# Adafruit_Feather_M0_Basic_rev_C.net
KiCad netlist of a schematic drawn in Altium Designer
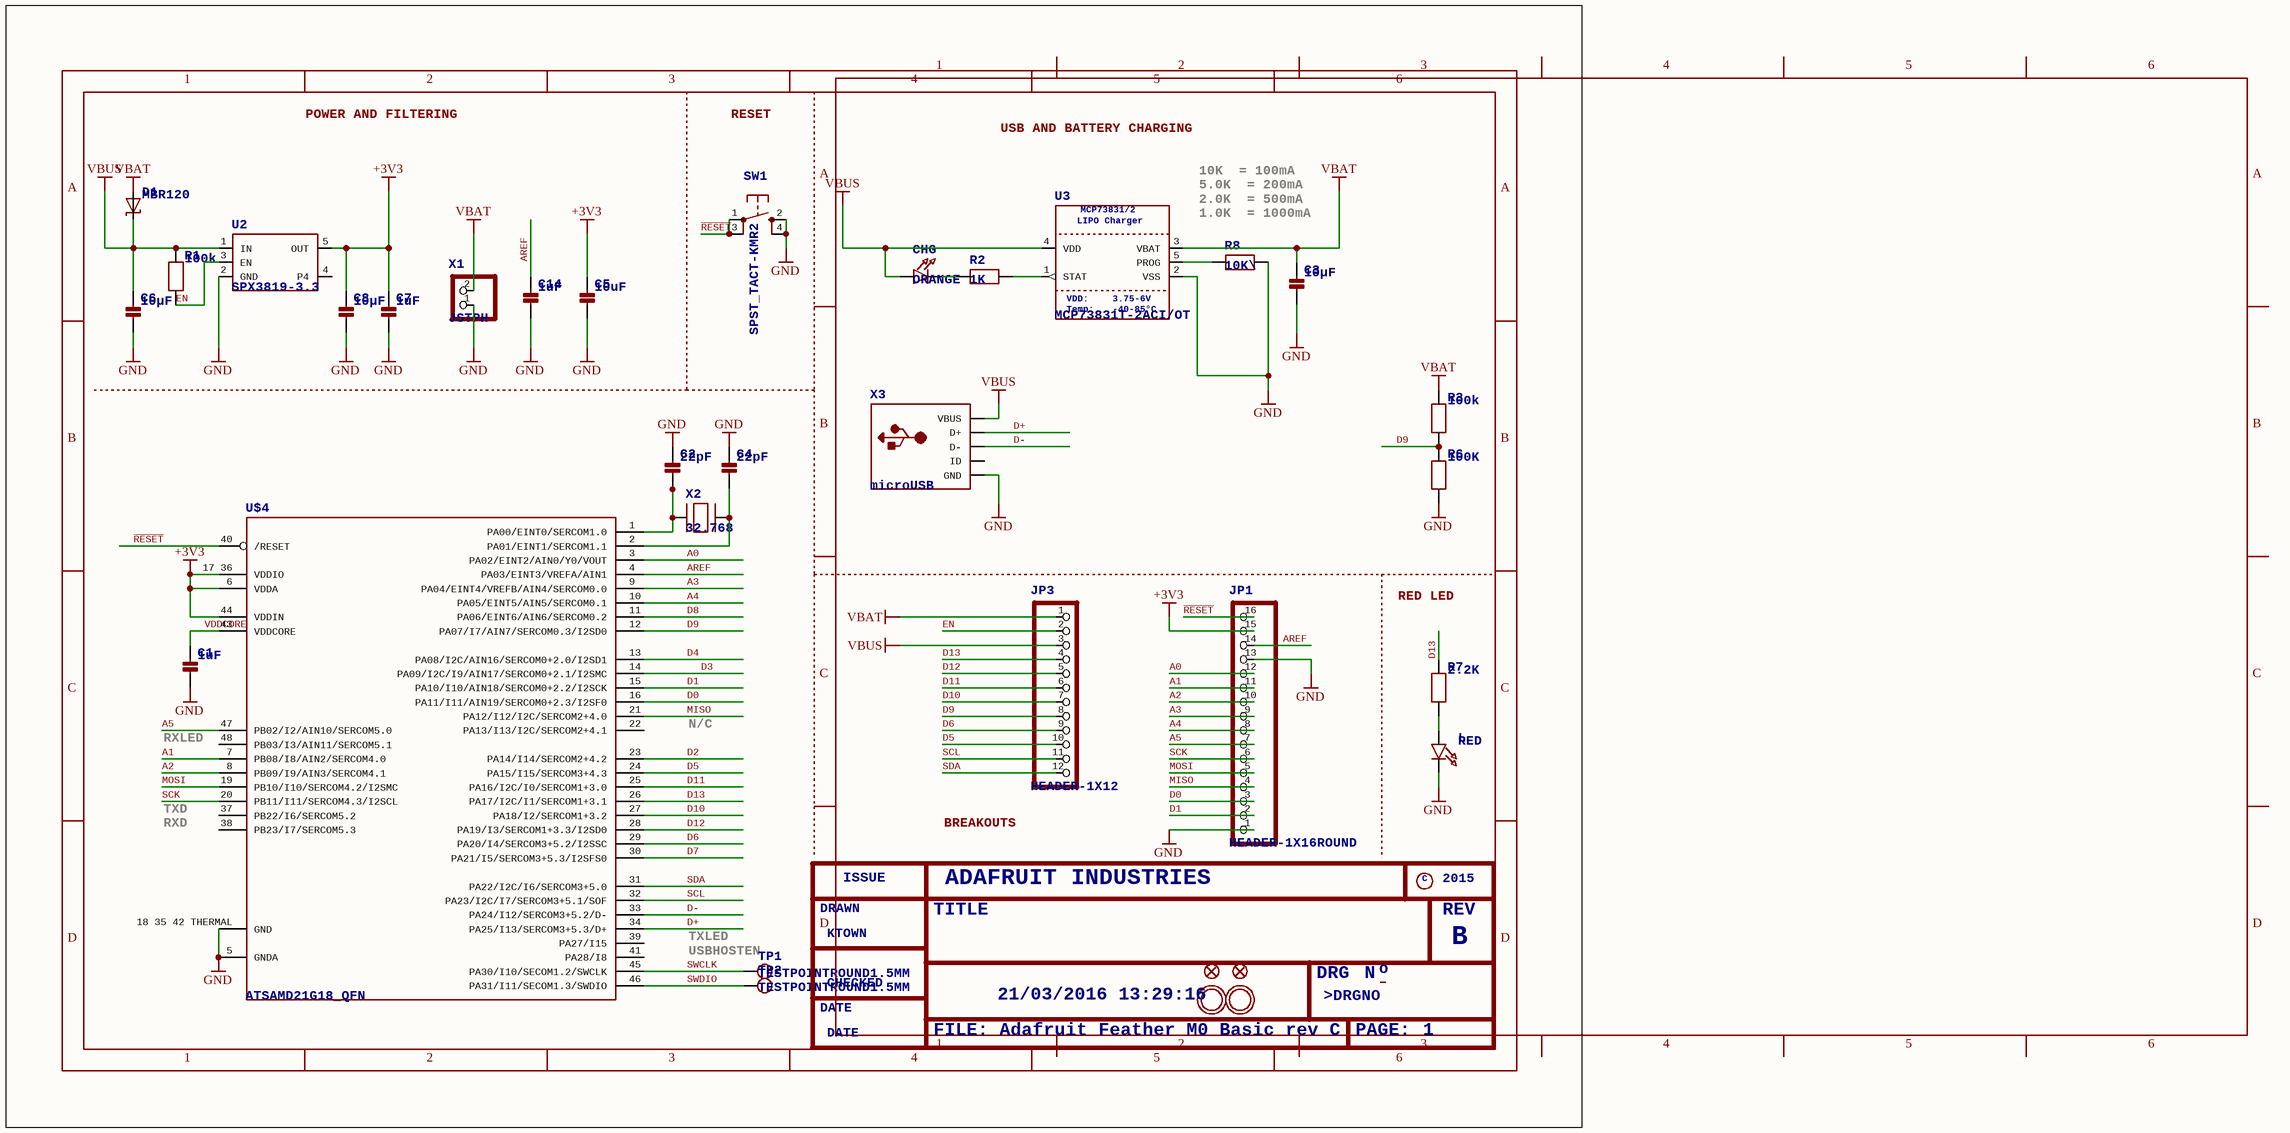
[diagram p0: Adafruit Feather M0 Basic rev C.SchDoc]

(export (version "E")
  (design (tool "Eeschema 10.0.6"))
  (components
    (comp (ref "C1")
      (value "1uF")
      (footprint "0603-NO")
      (fields (field (name "DRAWN") "KTOWN"))
      (libsource (lib "microbuilder") (part "CAP_CERAMIC0603_NO"))
    )
    (comp (ref "C2")
      (value "22pF")
      (footprint "0603-NO")
      (fields (field (name "DRAWN") "KTOWN"))
      (libsource (lib "") (part "CAP_CERAMIC0603_NO_1"))
    )
    (comp (ref "C3")
      (value "10µF")
      (footprint "0805-NO")
      (fields (field (name "DRAWN") "KTOWN"))
      (libsource (lib "microbuilder") (part "CAP_CERAMIC0805-NOOUTLINE"))
    )
    (comp (ref "C4")
      (value "22pF")
      (footprint "0603-NO")
      (fields (field (name "DRAWN") "KTOWN"))
      (libsource (lib "") (part "CAP_CERAMIC0603_NO_1"))
    )
    (comp (ref "C5")
      (value "10uF")
      (footprint "0805-NO")
      (fields (field (name "DRAWN") "KTOWN"))
      (libsource (lib "microbuilder") (part "CAP_CERAMIC0805-NOOUTLINE"))
    )
    (comp (ref "C6")
      (value "10µF")
      (footprint "0805-NO")
      (fields (field (name "DRAWN") "KTOWN"))
      (libsource (lib "microbuilder") (part "CAP_CERAMIC0805-NOOUTLINE"))
    )
    (comp (ref "C7")
      (value "1uF")
      (footprint "0603-NO")
      (fields (field (name "DRAWN") "KTOWN"))
      (libsource (lib "microbuilder") (part "CAP_CERAMIC0603_NO"))
    )
    (comp (ref "C8")
      (value "10µF")
      (footprint "0805-NO")
      (fields (field (name "DRAWN") "KTOWN"))
      (libsource (lib "microbuilder") (part "CAP_CERAMIC0805-NOOUTLINE"))
    )
    (comp (ref "C14")
      (value "1uF")
      (footprint "0603-NO")
      (fields (field (name "DRAWN") "KTOWN"))
      (libsource (lib "microbuilder") (part "CAP_CERAMIC0603_NO"))
    )
    (comp (ref "CHG")
      (value "ORANGE")
      (footprint "CHIPLED_0805_NOOUTLINE")
      (fields (field (name "DRAWN") "KTOWN"))
      (libsource (lib "") (part "LED0805_NOOUTLINE_1"))
    )
    (comp (ref "D1")
      (value "MBR120")
      (footprint "SOD-123")
      (fields (field (name "DRAWN") "KTOWN"))
      (libsource (lib "microbuilder") (part "DIODE-SCHOTTKYSOD-123"))
    )
    (comp (ref "FRAME1")
      (value "FRAME_A4")
      (description "FRAME   DIN A4, landscape with location and doc. field")
      (fields
        (field (name "SHEET") "1")
        (field (name "REV") "REV")
        (field (name "TITLE") "TITLE")
        (field (name "DRG") "DRG")
        (field (name "O") "o")
        (field (name "DRAWING_NAME") "Adafruit Feather M0 Basic rev C")
        (field (name "N") "N")
        (field (name "LAST_DATE_TIME") "21/03/2016 13:29:16")
        (field (name "2015") "2015")
        (field (name "C") "C")
        (field (name "ISSUE") "ISSUE")
        (field (name "DRAWN") "DRAWN")
        (field (name "DATE") "DATE")
        (field (name "COMPANY") "ADAFRUIT INDUSTRIES")
        (field (name "FILE") "FILE:")
        (field (name "PAGE") "PAGE:")
        (field (name "DRAWN_1") "KTOWN")
        (field (name "CHECKED") "CHECKED")
        (field (name "DATE_1") "DATE")
        (field (name "DRGNO") ">DRGNO")
        (field (name "REV_1") "B")
      )
      (libsource (lib "microbuilder") (part "FRAME_A4"))
    )
    (comp (ref "JP1")
      (value "HEADER-1X16ROUND")
      (footprint "1X16_ROUND")
      (description "PIN HEADER")
      (fields (field (name "DRAWN") "KTOWN"))
      (libsource (lib "microbuilder") (part "HEADER-1X16ROUND"))
    )
    (comp (ref "JP3")
      (value "HEADER-1X12")
      (footprint "1X12_ROUND")
      (fields (field (name "DRAWN") "KTOWN"))
      (libsource (lib "microbuilder") (part "HEADER-1X12"))
    )
    (comp (ref "L")
      (value "RED")
      (footprint "CHIPLED_0805_NOOUTLINE")
      (fields (field (name "DRAWN") "KTOWN"))
      (libsource (lib "microbuilder") (part "LED0805_NOOUTLINE"))
    )
    (comp (ref "R1")
      (value "100k")
      (footprint "0603-NO")
      (fields (field (name "DRAWN") "KTOWN"))
      (libsource (lib "microbuilder") (part "RESISTOR_0603_NOOUT"))
    )
    (comp (ref "R2")
      (value "1K")
      (footprint "0603-NO")
      (fields (field (name "DRAWN") "KTOWN"))
      (libsource (lib "microbuilder") (part "RESISTOR_0603_NOOUT"))
    )
    (comp (ref "R3")
      (value "100k")
      (footprint "0603-NO")
      (fields (field (name "DRAWN") "KTOWN"))
      (libsource (lib "microbuilder") (part "RESISTOR_0603_NOOUT"))
    )
    (comp (ref "R6")
      (value "100K")
      (footprint "0603-NO")
      (fields (field (name "DRAWN") "KTOWN"))
      (libsource (lib "microbuilder") (part "RESISTOR_0603_NOOUT"))
    )
    (comp (ref "R7")
      (value "2.2K")
      (footprint "0603-NO")
      (fields (field (name "DRAWN") "KTOWN"))
      (libsource (lib "microbuilder") (part "RESISTOR_0603_NOOUT"))
    )
    (comp (ref "R8")
      (value "10~{K}")
      (footprint "0603-NO")
      (fields (field (name "DRAWN") "KTOWN"))
      (libsource (lib "microbuilder") (part "RESISTOR_0603_NOOUT"))
    )
    (comp (ref "SW1")
      (value "SPST_TACT-KMR2")
      (footprint "KMR2")
      (description "SMT 6mm switch, EVQQ2 series    http://www.ladyada.net/library/eagle")
      (libsource (lib "adafruit") (part "SPST_TACT-KMR2"))
    )
    (comp (ref "TP1")
      (value "TESTPOINTROUND1.5MM")
      (footprint "TESTPOINT_ROUND_1.5MM")
      (fields (field (name "DRAWN") "KTOWN"))
      (libsource (lib "microbuilder") (part "TESTPOINTROUND1.5MM"))
    )
    (comp (ref "TP2")
      (value "TESTPOINTROUND1.5MM")
      (footprint "TESTPOINT_ROUND_1.5MM")
      (fields (field (name "DRAWN") "KTOWN"))
      (libsource (lib "microbuilder") (part "TESTPOINTROUND1.5MM"))
    )
    (comp (ref "U$4")
      (value "ATSAMD21G18_QFN")
      (footprint "TQFN48_7MM")
      (fields (field (name "DRAWN") "KTOWN"))
      (libsource (lib "microbuilder") (part "ATSAMD21J_QFN"))
    )
    (comp (ref "U$31")
      (value "MOUNTINGHOLE2.5")
      (footprint "MOUNTINGHOLE_2.5_PLATED")
      (description "Mounting Hole   For #2 screws (0.086\"/2.18mm width, 0.094\"/2.4mm hole) use 2.5mm")
      (fields (field (name "DRAWN") "KTOWN"))
      (libsource (lib "microbuilder") (part "MOUNTINGHOLE2.5"))
    )
    (comp (ref "U$32")
      (value "MOUNTINGHOLE2.5")
      (footprint "MOUNTINGHOLE_2.5_PLATED")
      (description "Mounting Hole   For #2 screws (0.086\"/2.18mm width, 0.094\"/2.4mm hole) use 2.5mm")
      (fields (field (name "DRAWN") "KTOWN"))
      (libsource (lib "microbuilder") (part "MOUNTINGHOLE2.5"))
    )
    (comp (ref "U$34")
      (value "FIDUCIAL\"\"")
      (footprint "FIDUCIAL_1MM")
      (description "Fiducial Alignment Points   Various fiducial points for machine vision alignment.")
      (fields (field (name "DRAWN") "KTOWN"))
      (libsource (lib "microbuilder") (part "FIDUCIAL{dblquote}{dblquote}"))
    )
    (comp (ref "U$35")
      (value "FIDUCIAL\"\"")
      (footprint "FIDUCIAL_1MM")
      (description "Fiducial Alignment Points   Various fiducial points for machine vision alignment.")
      (fields (field (name "DRAWN") "KTOWN"))
      (libsource (lib "microbuilder") (part "FIDUCIAL{dblquote}{dblquote}"))
    )
    (comp (ref "U2")
      (value "SPX3819-3.3")
      (footprint "SOT23-5")
      (fields (field (name "DRAWN") "KTOWN"))
      (libsource (lib "microbuilder") (part "VREG_SOT23-5"))
    )
    (comp (ref "U3")
      (value "MCP73831T-2ACI/OT")
      (footprint "SOT23-5")
      (fields
        (field (name "MCP73831/2") "MCP73831/2")
        (field (name "LIPOCHARGER") "LIPO Charger")
        (field (name "TEMP") "Temp:")
        (field (name "-40-85°C") "-40-85°C")
        (field (name "VDD") "VDD:")
        (field (name "3.75-6V") "3.75-6V")
        (field (name "DRAWN") "KTOWN")
      )
      (libsource (lib "microbuilder") (part "MCP73831/2"))
    )
    (comp (ref "X1")
      (value "JSTPH")
      (footprint "JSTPH2")
      (description "JST 2-Pin Right-Angle Connector  PH-Series - 4UConnector: 17311  SH-Series - 4UConnector: 07278")
      (fields (field (name "DRAWN") "KTOWN"))
      (libsource (lib "microbuilder") (part "CON_JST_PH_2PIN"))
    )
    (comp (ref "X2")
      (value "32.768")
      (footprint "XTAL3215")
      (description "Low cost SMT crystals, no capacitors included    http://www.ladyada.net/library/eagle")
      (fields (field (name "DRAWN") "KTOWN"))
      (libsource (lib "adafruit2") (part "XTAL-3.2X1.5"))
    )
    (comp (ref "X3")
      (value "microUSB")
      (footprint "4UCONN_20329_V2")
      (description "USB ConnectorsUSBMINIB - Surface Mount Female Mini-B USB Connector    4UConnector: 06564")
      (fields (field (name "DRAWN") "KTOWN"))
      (libsource (lib "microbuilder") (part "USB_MICRO_20329_V2"))
    )
  )
  (nets
    (net (code "1") (name "+3V3") (class "Default")
      (node (ref "C5") (pin "1") (pinfunction "1_1") (pintype "passive"))
      (node (ref "C7") (pin "1") (pinfunction "1_1") (pintype "passive"))
      (node (ref "C8") (pin "1") (pinfunction "1_1") (pintype "passive"))
      (node (ref "JP1") (pin "15") (pinfunction "15_15") (pintype "passive"))
      (node (ref "U$4") (pin "17_36") (pinfunction "VDDIO_17_36") (pintype "power_in"))
      (node (ref "U$4") (pin "44") (pinfunction "VDDIN_44") (pintype "power_in"))
      (node (ref "U$4") (pin "6") (pinfunction "VDDA_6") (pintype "power_in"))
      (node (ref "U2") (pin "5") (pinfunction "OUT_5") (pintype "open_emitter"))
    )
    (net (code "2") (name "/A0") (class "Default")
      (node (ref "JP1") (pin "12") (pinfunction "12_12") (pintype "passive"))
      (node (ref "U$4") (pin "3") (pinfunction "PA02/EINT2/AIN0/Y0/VOUT_3") (pintype "passive"))
    )
    (net (code "3") (name "/A1") (class "Default")
      (node (ref "JP1") (pin "11") (pinfunction "11_11") (pintype "passive"))
      (node (ref "U$4") (pin "7") (pinfunction "PB08/I8/AIN2/SERCOM4.0_7") (pintype "passive"))
    )
    (net (code "4") (name "/A2") (class "Default")
      (node (ref "JP1") (pin "10") (pinfunction "10_10") (pintype "passive"))
      (node (ref "U$4") (pin "8") (pinfunction "PB09/I9/AIN3/SERCOM4.1_8") (pintype "passive"))
    )
    (net (code "5") (name "/A3") (class "Default")
      (node (ref "JP1") (pin "9") (pinfunction "9_9") (pintype "passive"))
      (node (ref "U$4") (pin "9") (pinfunction "PA04/EINT4/VREFB/AIN4/SERCOM0.0_9") (pintype "passive"))
    )
    (net (code "6") (name "/A4") (class "Default")
      (node (ref "JP1") (pin "8") (pinfunction "8_8") (pintype "passive"))
      (node (ref "U$4") (pin "10") (pinfunction "PA05/EINT5/AIN5/SERCOM0.1_10") (pintype "passive"))
    )
    (net (code "7") (name "/A5") (class "Default")
      (node (ref "JP1") (pin "7") (pinfunction "7_7") (pintype "passive"))
      (node (ref "U$4") (pin "47") (pinfunction "PB02/I2/AIN10/SERCOM5.0_47") (pintype "passive"))
    )
    (net (code "8") (name "/AREF") (class "Default")
      (node (ref "C14") (pin "1") (pinfunction "1_1") (pintype "passive"))
      (node (ref "JP1") (pin "14") (pinfunction "14_14") (pintype "passive"))
      (node (ref "U$4") (pin "4") (pinfunction "PA03/EINT3/VREFA/AIN1_4") (pintype "passive"))
    )
    (net (code "9") (name "/D+") (class "Default")
      (node (ref "U$4") (pin "34") (pinfunction "PA25/I13/SERCOM3+5.3/D+_34") (pintype "passive"))
      (node (ref "X3") (pin "D+") (pinfunction "D+_D+") (pintype "passive"))
    )
    (net (code "10") (name "/D-") (class "Default")
      (node (ref "U$4") (pin "33") (pinfunction "PA24/I12/SERCOM3+5.2/D-_33") (pintype "passive"))
      (node (ref "X3") (pin "D-") (pinfunction "D-_D-") (pintype "passive"))
    )
    (net (code "11") (name "/D0") (class "Default")
      (node (ref "JP1") (pin "3") (pinfunction "3_3") (pintype "passive"))
      (node (ref "U$4") (pin "16") (pinfunction "PA11/I11/AIN19/SERCOM0+2.3/I2SF0_16") (pintype "passive"))
    )
    (net (code "12") (name "/D1") (class "Default")
      (node (ref "JP1") (pin "2") (pinfunction "2_2") (pintype "passive"))
      (node (ref "U$4") (pin "15") (pinfunction "PA10/I10/AIN18/SERCOM0+2.2/I2SCK_15") (pintype "passive"))
    )
    (net (code "13") (name "/D2") (class "Default")
      (node (ref "U$4") (pin "23") (pinfunction "PA14/I14/SERCOM2+4.2_23") (pintype "passive"))
    )
    (net (code "14") (name "/D3") (class "Default")
      (node (ref "U$4") (pin "14") (pinfunction "PA09/I2C/I9/AIN17/SERCOM0+2.1/I2SMC_14") (pintype "passive"))
    )
    (net (code "15") (name "/D4") (class "Default")
      (node (ref "U$4") (pin "13") (pinfunction "PA08/I2C/AIN16/SERCOM0+2.0/I2SD1_13") (pintype "passive"))
    )
    (net (code "16") (name "/D5") (class "Default")
      (node (ref "JP3") (pin "10") (pinfunction "10_10") (pintype "passive"))
      (node (ref "U$4") (pin "24") (pinfunction "PA15/I15/SERCOM3+4.3_24") (pintype "passive"))
    )
    (net (code "17") (name "/D6") (class "Default")
      (node (ref "JP3") (pin "9") (pinfunction "9_9") (pintype "passive"))
      (node (ref "U$4") (pin "29") (pinfunction "PA20/I4/SERCOM3+5.2/I2SSC_29") (pintype "passive"))
    )
    (net (code "18") (name "/D7") (class "Default")
      (node (ref "U$4") (pin "30") (pinfunction "PA21/I5/SERCOM3+5.3/I2SFS0_30") (pintype "passive"))
    )
    (net (code "19") (name "/D8") (class "Default")
      (node (ref "U$4") (pin "11") (pinfunction "PA06/EINT6/AIN6/SERCOM0.2_11") (pintype "passive"))
    )
    (net (code "20") (name "/D9") (class "Default")
      (node (ref "JP3") (pin "8") (pinfunction "8_8") (pintype "passive"))
      (node (ref "R3") (pin "2") (pinfunction "2_2") (pintype "passive"))
      (node (ref "R6") (pin "1") (pinfunction "1_1") (pintype "passive"))
      (node (ref "U$4") (pin "12") (pinfunction "PA07/I7/AIN7/SERCOM0.3/I2SD0_12") (pintype "passive"))
    )
    (net (code "21") (name "/D10") (class "Default")
      (node (ref "JP3") (pin "7") (pinfunction "7_7") (pintype "passive"))
      (node (ref "U$4") (pin "27") (pinfunction "PA18/I2/SERCOM1+3.2_27") (pintype "passive"))
    )
    (net (code "22") (name "/D11") (class "Default")
      (node (ref "JP3") (pin "6") (pinfunction "6_6") (pintype "passive"))
      (node (ref "U$4") (pin "25") (pinfunction "PA16/I2C/I0/SERCOM1+3.0_25") (pintype "passive"))
    )
    (net (code "23") (name "/D12") (class "Default")
      (node (ref "JP3") (pin "5") (pinfunction "5_5") (pintype "passive"))
      (node (ref "U$4") (pin "28") (pinfunction "PA19/I3/SERCOM1+3.3/I2SD0_28") (pintype "passive"))
    )
    (net (code "24") (name "/D13") (class "Default")
      (node (ref "JP3") (pin "4") (pinfunction "4_4") (pintype "passive"))
      (node (ref "R7") (pin "1") (pinfunction "1_1") (pintype "passive"))
      (node (ref "U$4") (pin "26") (pinfunction "PA17/I2C/I1/SERCOM1+3.1_26") (pintype "passive"))
    )
    (net (code "25") (name "/EN") (class "Default")
      (node (ref "JP3") (pin "2") (pinfunction "2_2") (pintype "passive"))
      (node (ref "R1") (pin "2") (pinfunction "2_2") (pintype "passive"))
      (node (ref "U2") (pin "3") (pinfunction "EN_3") (pintype "passive"))
    )
    (net (code "26") (name "/MISO") (class "Default")
      (node (ref "JP1") (pin "4") (pinfunction "4_4") (pintype "passive"))
      (node (ref "U$4") (pin "21") (pinfunction "PA12/I12/I2C/SERCOM2+4.0_21") (pintype "passive"))
    )
    (net (code "27") (name "/MOSI") (class "Default")
      (node (ref "JP1") (pin "5") (pinfunction "5_5") (pintype "passive"))
      (node (ref "U$4") (pin "19") (pinfunction "PB10/I10/SERCOM4.2/I2SMC_19") (pintype "passive"))
    )
    (net (code "28") (name "/SCK") (class "Default")
      (node (ref "JP1") (pin "6") (pinfunction "6_6") (pintype "passive"))
      (node (ref "U$4") (pin "20") (pinfunction "PB11/I11/SERCOM4.3/I2SCL_20") (pintype "passive"))
    )
    (net (code "29") (name "/SCL") (class "Default")
      (node (ref "JP3") (pin "11") (pinfunction "11_11") (pintype "passive"))
      (node (ref "U$4") (pin "32") (pinfunction "PA23/I2C/I7/SERCOM3+5.1/SOF_32") (pintype "passive"))
    )
    (net (code "30") (name "/SDA") (class "Default")
      (node (ref "JP3") (pin "12") (pinfunction "12_12") (pintype "passive"))
      (node (ref "U$4") (pin "31") (pinfunction "PA22/I2C/I6/SERCOM3+5.0_31") (pintype "passive"))
    )
    (net (code "31") (name "/SWCLK") (class "Default")
      (node (ref "TP1") (pin "P$1") (pinfunction "P$1_P$1") (pintype "passive"))
      (node (ref "U$4") (pin "45") (pinfunction "PA30/I10/SECOM1.2/SWCLK_45") (pintype "passive"))
    )
    (net (code "32") (name "/SWDIO") (class "Default")
      (node (ref "TP2") (pin "P$1") (pinfunction "P$1_P$1") (pintype "passive"))
      (node (ref "U$4") (pin "46") (pinfunction "PA31/I11/SECOM1.3/SWDIO_46") (pintype "passive"))
    )
    (net (code "33") (name "/VDDCORE") (class "Default")
      (node (ref "C1") (pin "1") (pinfunction "1_1") (pintype "passive"))
      (node (ref "U$4") (pin "43") (pinfunction "VDDCORE_43") (pintype "power_in"))
    )
    (net (code "34") (name "/~{RESET}") (class "Default")
      (node (ref "JP1") (pin "16") (pinfunction "16_16") (pintype "passive"))
      (node (ref "SW1") (pin "1") (pinfunction "P_1") (pintype "passive"))
      (node (ref "SW1") (pin "3") (pinfunction "P1_3") (pintype "passive"))
      (node (ref "U$4") (pin "40") (pinfunction "/RESET_40") (pintype "passive"))
    )
    (net (code "35") (name "GND") (class "Default")
      (node (ref "C1") (pin "2") (pinfunction "2_2") (pintype "passive"))
      (node (ref "C14") (pin "2") (pinfunction "2_2") (pintype "passive"))
      (node (ref "C2") (pin "2") (pinfunction "2_2") (pintype "passive"))
      (node (ref "C3") (pin "2") (pinfunction "2_2") (pintype "passive"))
      (node (ref "C4") (pin "2") (pinfunction "2_2") (pintype "passive"))
      (node (ref "C5") (pin "2") (pinfunction "2_2") (pintype "passive"))
      (node (ref "C6") (pin "2") (pinfunction "2_2") (pintype "passive"))
      (node (ref "C7") (pin "2") (pinfunction "2_2") (pintype "passive"))
      (node (ref "C8") (pin "2") (pinfunction "2_2") (pintype "passive"))
      (node (ref "JP1") (pin "1") (pinfunction "1_1") (pintype "passive"))
      (node (ref "JP1") (pin "13") (pinfunction "13_13") (pintype "passive"))
      (node (ref "L") (pin "C") (pinfunction "C_C") (pintype "passive"))
      (node (ref "R6") (pin "2") (pinfunction "2_2") (pintype "passive"))
      (node (ref "R8") (pin "2") (pinfunction "2_2") (pintype "passive"))
      (node (ref "SW1") (pin "2") (pinfunction "S_2") (pintype "passive"))
      (node (ref "SW1") (pin "4") (pinfunction "S1_4") (pintype "passive"))
      (node (ref "U$4") (pin "18_35_42_THERMAL") (pinfunction "GND_18_35_42_THERMAL") (pintype "power_in"))
      (node (ref "U$4") (pin "5") (pinfunction "GNDA_5") (pintype "power_in"))
      (node (ref "U2") (pin "2") (pinfunction "GND_2") (pintype "power_in"))
      (node (ref "U3") (pin "2") (pinfunction "VSS_2") (pintype "power_in"))
      (node (ref "X1") (pin "1") (pinfunction "1_1") (pintype "passive"))
      (node (ref "X3") (pin "BASE@1_BASE@2_GND_SPRT@1_SPRT@2_SPRT@3_SPRT@4") (pinfunction "GND_BASE@1_BASE@2_GND_SPRT@1_SPRT@2_SPRT@3_SPRT@4") (pintype "power_in"))
    )
    (net (code "36") (name "Net-(CHG-PadC)") (class "Default")
      (node (ref "CHG") (pin "C") (pinfunction "C_C") (pintype "passive"))
      (node (ref "R2") (pin "1") (pinfunction "1_1") (pintype "passive"))
    )
    (net (code "37") (name "Net-(L-PadA)") (class "Default")
      (node (ref "L") (pin "A") (pinfunction "A_A") (pintype "passive"))
      (node (ref "R7") (pin "2") (pinfunction "2_2") (pintype "passive"))
    )
    (net (code "38") (name "Net-(U$4-PA00{slash}EINT0{slash}SERCOM1.0)") (class "Default")
      (node (ref "C2") (pin "1") (pinfunction "1_1") (pintype "passive"))
      (node (ref "U$4") (pin "1") (pinfunction "PA00/EINT0/SERCOM1.0_1") (pintype "passive"))
      (node (ref "X2") (pin "P$1") (pinfunction "P$1_P$1") (pintype "passive"))
    )
    (net (code "39") (name "Net-(U$4-PA01{slash}EINT1{slash}SERCOM1.1)") (class "Default")
      (node (ref "C4") (pin "1") (pinfunction "1_1") (pintype "passive"))
      (node (ref "U$4") (pin "2") (pinfunction "PA01/EINT1/SERCOM1.1_2") (pintype "passive"))
      (node (ref "X2") (pin "P$2") (pinfunction "P$2_P$2") (pintype "passive"))
    )
    (net (code "40") (name "Net-(U3-PROG)") (class "Default")
      (node (ref "R8") (pin "1") (pinfunction "1_1") (pintype "passive"))
      (node (ref "U3") (pin "5") (pinfunction "PROG_5") (pintype "passive"))
    )
    (net (code "41") (name "Net-(U3-STAT)") (class "Default")
      (node (ref "R2") (pin "2") (pinfunction "2_2") (pintype "passive"))
      (node (ref "U3") (pin "1") (pinfunction "STAT_1") (pintype "output"))
    )
    (net (code "42") (name "VBAT") (class "Default")
      (node (ref "C3") (pin "1") (pinfunction "1_1") (pintype "passive"))
      (node (ref "D1") (pin "A") (pinfunction "A_A") (pintype "passive"))
      (node (ref "JP3") (pin "1") (pinfunction "1_1") (pintype "passive"))
      (node (ref "R3") (pin "1") (pinfunction "1_1") (pintype "passive"))
      (node (ref "U3") (pin "3") (pinfunction "VBAT_3") (pintype "power_in"))
      (node (ref "X1") (pin "2") (pinfunction "2_2") (pintype "passive"))
    )
    (net (code "43") (name "VBUS") (class "Default")
      (node (ref "C6") (pin "1") (pinfunction "1_1") (pintype "passive"))
      (node (ref "CHG") (pin "A") (pinfunction "A_A") (pintype "passive"))
      (node (ref "D1") (pin "C") (pinfunction "C_C") (pintype "passive"))
      (node (ref "JP3") (pin "3") (pinfunction "3_3") (pintype "passive"))
      (node (ref "R1") (pin "1") (pinfunction "1_1") (pintype "passive"))
      (node (ref "U2") (pin "1") (pinfunction "IN_1") (pintype "power_in"))
      (node (ref "U3") (pin "4") (pinfunction "VDD_4") (pintype "power_in"))
      (node (ref "X3") (pin "VBUS") (pinfunction "VBUS_VBUS") (pintype "power_in"))
    )
    (net (code "44") (name "unconnected-(U$4-PA13{slash}I13{slash}I2C{slash}SERCOM2+4.1-Pad22)") (class "Default")
      (node (ref "U$4") (pin "22") (pinfunction "PA13/I13/I2C/SERCOM2+4.1_22") (pintype "passive"))
    )
    (net (code "45") (name "unconnected-(U$4-PA27{slash}I15-Pad39)") (class "Default")
      (node (ref "U$4") (pin "39") (pinfunction "PA27/I15_39") (pintype "passive"))
    )
    (net (code "46") (name "unconnected-(U$4-PA28{slash}I8-Pad41)") (class "Default")
      (node (ref "U$4") (pin "41") (pinfunction "PA28/I8_41") (pintype "passive"))
    )
    (net (code "47") (name "unconnected-(U$4-PB03{slash}I3{slash}AIN11{slash}SERCOM5.1-Pad48)") (class "Default")
      (node (ref "U$4") (pin "48") (pinfunction "PB03/I3/AIN11/SERCOM5.1_48") (pintype "passive"))
    )
    (net (code "48") (name "unconnected-(U$4-PB22{slash}I6{slash}SERCOM5.2-Pad37)") (class "Default")
      (node (ref "U$4") (pin "37") (pinfunction "PB22/I6/SERCOM5.2_37") (pintype "passive"))
    )
    (net (code "49") (name "unconnected-(U$4-PB23{slash}I7{slash}SERCOM5.3-Pad38)") (class "Default")
      (node (ref "U$4") (pin "38") (pinfunction "PB23/I7/SERCOM5.3_38") (pintype "passive"))
    )
    (net (code "50") (name "unconnected-(U2-P4-Pad4)") (class "Default")
      (node (ref "U2") (pin "4") (pinfunction "P4_4") (pintype "passive"))
    )
    (net (code "51") (name "unconnected-(X3-PadID)") (class "Default")
      (node (ref "X3") (pin "ID") (pinfunction "ID_ID") (pintype "passive"))
    )
  )
)
